# ranback_top.net
KiCad netlist of a schematic drawn in EAGLE
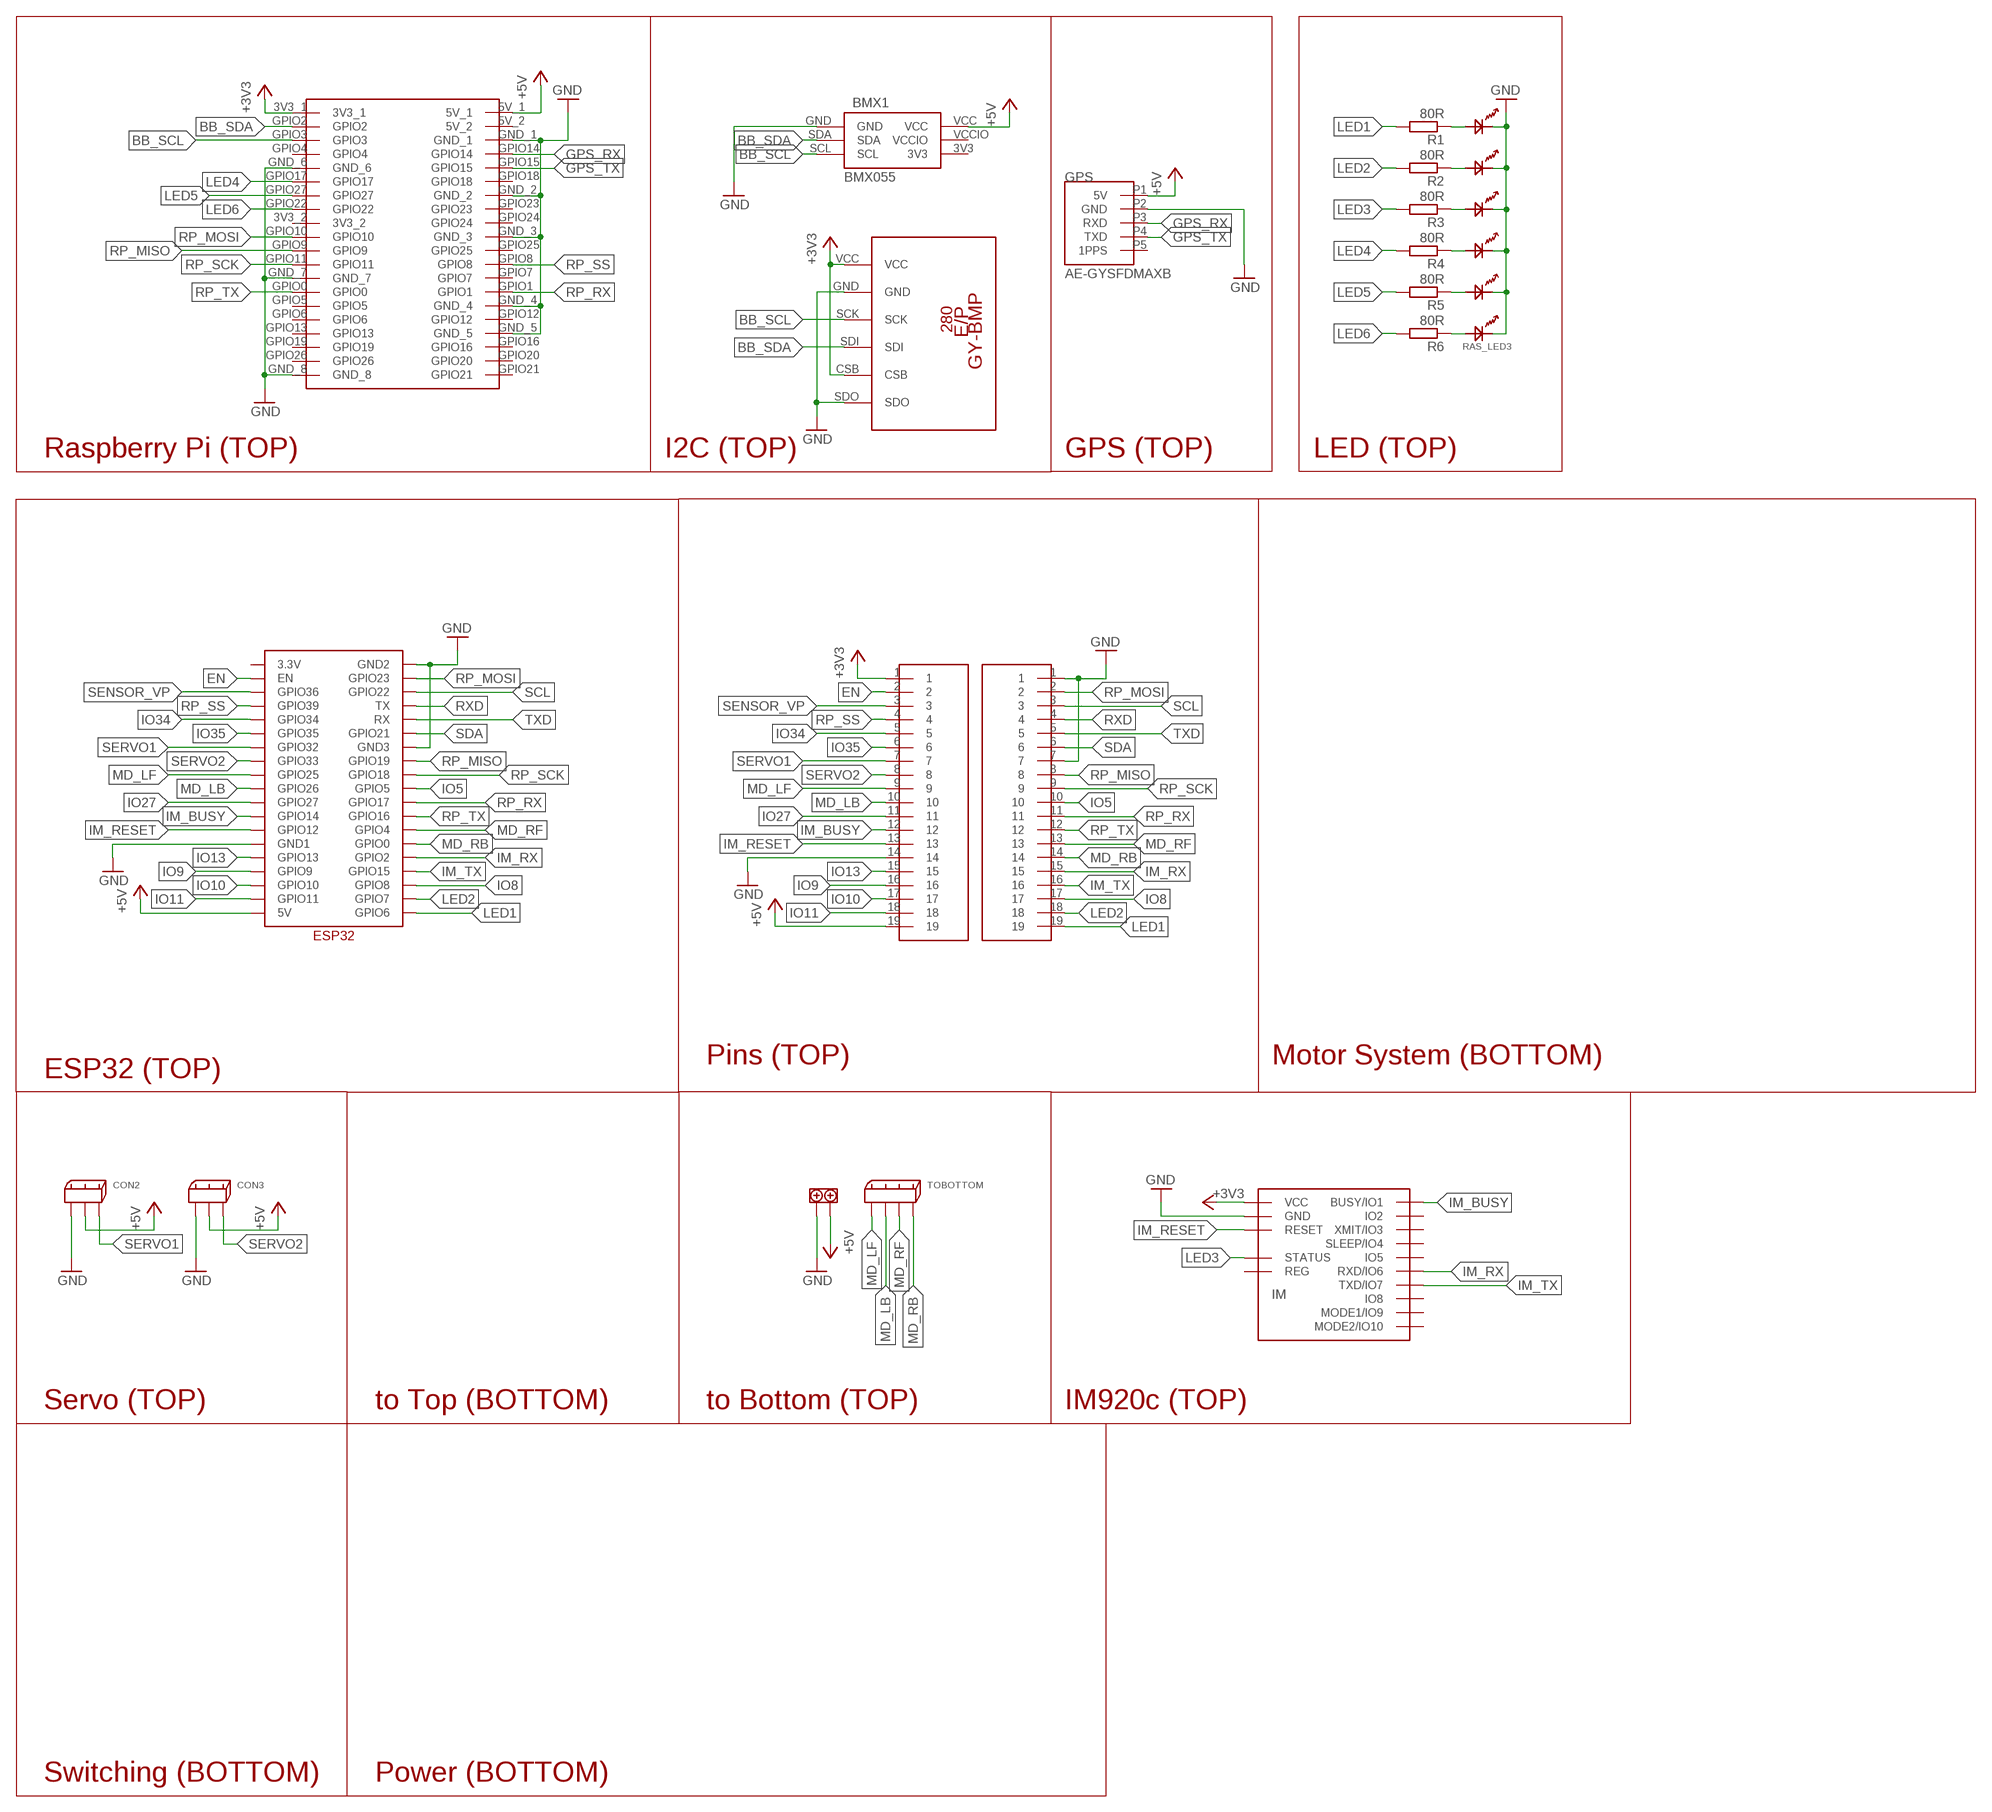
[diagram p0: schematic, sheet 1]

(export (version "E")
  (design (tool "Eeschema 10.0.6"))
  (components
    (comp (ref "BMX1")
      (value "BMX055")
      (footprint "eagle-import:BMX055")
      (libsource (lib "eagle-import") (part "BMX055"))
    )
    (comp (ref "CON2")
      (value "2.5_MINI-SPOX_3PIN")
      (footprint "eagle-import:2.5_MINI-SPOX_3PIN")
      (libsource (lib "eagle-import") (part "2.5_MINI-SPOX_3PIN"))
    )
    (comp (ref "CON3")
      (value "2.5_MINI-SPOX_3PIN")
      (footprint "eagle-import:2.5_MINI-SPOX_3PIN")
      (libsource (lib "eagle-import") (part "2.5_MINI-SPOX_3PIN"))
    )
    (comp (ref "ESP_LED1")
      (value "OSXX1608C1A")
      (footprint "eagle-import:OSXX1608C1A")
      (libsource (lib "eagle-import") (part "OSXX1608C1A"))
    )
    (comp (ref "ESP_LED2")
      (value "OSXX1608C1A")
      (footprint "eagle-import:OSXX1608C1A")
      (libsource (lib "eagle-import") (part "OSXX1608C1A"))
    )
    (comp (ref "GPS")
      (value "AE-GYSFDMAXB")
      (footprint "eagle-import:AE-GYSFDMAXB")
      (libsource (lib "eagle-import") (part "AE-GYSFDMAXB"))
    )
    (comp (ref "IM")
      (value "IM920C")
      (footprint "eagle-import:IM920C")
      (libsource (lib "eagle-import") (part "IM920C"))
    )
    (comp (ref "IMCHECK")
      (value "OSXX1608C1A")
      (footprint "eagle-import:OSXX1608C1A")
      (libsource (lib "eagle-import") (part "OSXX1608C1A"))
    )
    (comp (ref "PIN_L")
      (value "19_2.54")
      (footprint "eagle-import:19_2.54")
      (libsource (lib "eagle-import") (part "19_2.54"))
    )
    (comp (ref "PIN_R")
      (value "19_2.54")
      (footprint "eagle-import:19_2.54")
      (libsource (lib "eagle-import") (part "19_2.54"))
    )
    (comp (ref "R1")
      (value "80R")
      (footprint "eagle-import:0207_10")
      (libsource (lib "eagle-import") (part "R-EU_0207/10"))
    )
    (comp (ref "R2")
      (value "80R")
      (footprint "eagle-import:0207_10")
      (libsource (lib "eagle-import") (part "R-EU_0207/10"))
    )
    (comp (ref "R3")
      (value "80R")
      (footprint "eagle-import:0207_10")
      (libsource (lib "eagle-import") (part "R-EU_0207/10"))
    )
    (comp (ref "R4")
      (value "80R")
      (footprint "eagle-import:0207_10")
      (libsource (lib "eagle-import") (part "R-EU_0207/10"))
    )
    (comp (ref "R5")
      (value "80R")
      (footprint "eagle-import:0207_10")
      (libsource (lib "eagle-import") (part "R-EU_0207/10"))
    )
    (comp (ref "R6")
      (value "80R")
      (footprint "eagle-import:0207_10")
      (libsource (lib "eagle-import") (part "R-EU_0207/10"))
    )
    (comp (ref "RASPBERRYPI_4B")
      (value "RASPBERRYPI4B")
      (footprint "eagle-import:RASPBERRYPI4B")
      (libsource (lib "eagle-import") (part "RASPBERRYPI4B"))
    )
    (comp (ref "RAS_LED1")
      (value "OSXX1608C1A")
      (footprint "eagle-import:OSXX1608C1A")
      (libsource (lib "eagle-import") (part "OSXX1608C1A"))
    )
    (comp (ref "RAS_LED2")
      (value "OSXX1608C1A")
      (footprint "eagle-import:OSXX1608C1A")
      (libsource (lib "eagle-import") (part "OSXX1608C1A"))
    )
    (comp (ref "RAS_LED3")
      (value "OSXX1608C1A")
      (footprint "eagle-import:OSXX1608C1A")
      (libsource (lib "eagle-import") (part "OSXX1608C1A"))
    )
    (comp (ref "TM5")
      (value "TERMINAL_SLOPED_2PIN")
      (footprint "eagle-import:TERMINAL_SLOPED_2PIN")
      (libsource (lib "eagle-import") (part "TERMINAL_SLOPED_2PIN"))
    )
    (comp (ref "TOBOTTOM")
      (value "2.5_MINI-SPOX_4PIN")
      (footprint "eagle-import:2.5_MINI-SPOX_4PIN")
      (libsource (lib "eagle-import") (part "2.5_MINI-SPOX_4PIN"))
    )
    (comp (ref "U$2")
      (value "ESP32")
      (footprint "eagle-import:ESP32")
      (libsource (lib "eagle-import") (part "ESP32"))
    )
    (comp (ref "U$9")
      (value "GY-BPM280")
      (footprint "eagle-import:GY-BMP280-FOOTPRINT")
      (libsource (lib "eagle-import") (part "GY-BPM280"))
    )
  )
  (nets
    (net (code "1") (name "+3V3") (class "Default")
      (node (ref "IM") (pin "$P17") (pinfunction "VCC_$P17") (pintype "bidirectional"))
      (node (ref "PIN_L") (pin "1") (pinfunction "1_1") (pintype "bidirectional"))
      (node (ref "RASPBERRYPI_4B") (pin "3V3_1") (pinfunction "3V3_1_3V3_1") (pintype "bidirectional"))
      (node (ref "U$9") (pin "CSB") (pinfunction "CSB_CSB") (pintype "bidirectional"))
      (node (ref "U$9") (pin "VCC") (pinfunction "VCC_VCC") (pintype "bidirectional"))
    )
    (net (code "2") (name "+5V") (class "Default")
      (node (ref "BMX1") (pin "VCC") (pinfunction "VCC_VCC") (pintype "power_in"))
      (node (ref "CON2") (pin "2") (pinfunction "2_2") (pintype "bidirectional"))
      (node (ref "CON3") (pin "2") (pinfunction "2_2") (pintype "bidirectional"))
      (node (ref "GPS") (pin "P1") (pinfunction "5V_P1") (pintype "bidirectional"))
      (node (ref "PIN_L") (pin "19") (pinfunction "19_19") (pintype "bidirectional"))
      (node (ref "RASPBERRYPI_4B") (pin "5V_1") (pinfunction "5V_1_5V_1") (pintype "bidirectional"))
      (node (ref "TM5") (pin "1") (pinfunction "1_1") (pintype "bidirectional"))
      (node (ref "U$2") (pin "5V") (pinfunction "5V_5V") (pintype "bidirectional"))
    )
    (net (code "3") (name "/3V3") (class "Default")
      (node (ref "BMX1") (pin "3V3") (pinfunction "3V3_3V3") (pintype "power_in"))
    )
    (net (code "4") (name "/VCCIO") (class "Default")
      (node (ref "BMX1") (pin "VCCIO") (pinfunction "VCCIO_VCCIO") (pintype "power_in"))
    )
    (net (code "5") (name "BB_SCL") (class "Default")
      (node (ref "BMX1") (pin "SCL") (pinfunction "SCL_SCL") (pintype "bidirectional"))
      (node (ref "RASPBERRYPI_4B") (pin "GPIO3") (pinfunction "GPIO3_GPIO3") (pintype "bidirectional"))
      (node (ref "U$9") (pin "SCK") (pinfunction "SCK_SCK") (pintype "bidirectional"))
    )
    (net (code "6") (name "BB_SDA") (class "Default")
      (node (ref "BMX1") (pin "SDA") (pinfunction "SDA_SDA") (pintype "bidirectional"))
      (node (ref "RASPBERRYPI_4B") (pin "GPIO2") (pinfunction "GPIO2_GPIO2") (pintype "bidirectional"))
      (node (ref "U$9") (pin "SDI") (pinfunction "SDI_SDI") (pintype "bidirectional"))
    )
    (net (code "7") (name "EN") (class "Default")
      (node (ref "PIN_L") (pin "2") (pinfunction "2_2") (pintype "bidirectional"))
      (node (ref "U$2") (pin "EN") (pinfunction "EN_EN") (pintype "bidirectional"))
    )
    (net (code "8") (name "GND") (class "Default")
      (node (ref "BMX1") (pin "GND") (pinfunction "GND_GND") (pintype "power_in"))
      (node (ref "CON2") (pin "1") (pinfunction "1_1") (pintype "bidirectional"))
      (node (ref "CON3") (pin "1") (pinfunction "1_1") (pintype "bidirectional"))
      (node (ref "ESP_LED1") (pin "CT") (pinfunction "CT_CT") (pintype "bidirectional"))
      (node (ref "ESP_LED2") (pin "CT") (pinfunction "CT_CT") (pintype "bidirectional"))
      (node (ref "GPS") (pin "P2") (pinfunction "GND_P2") (pintype "bidirectional"))
      (node (ref "IM") (pin "$P18") (pinfunction "GND_$P18") (pintype "bidirectional"))
      (node (ref "IMCHECK") (pin "CT") (pinfunction "CT_CT") (pintype "bidirectional"))
      (node (ref "PIN_L") (pin "14") (pinfunction "14_14") (pintype "bidirectional"))
      (node (ref "PIN_R") (pin "1") (pinfunction "1_1") (pintype "bidirectional"))
      (node (ref "PIN_R") (pin "7") (pinfunction "7_7") (pintype "bidirectional"))
      (node (ref "RASPBERRYPI_4B") (pin "GND_1") (pinfunction "GND_1_GND_1") (pintype "bidirectional"))
      (node (ref "RASPBERRYPI_4B") (pin "GND_2") (pinfunction "GND_2_GND_2") (pintype "bidirectional"))
      (node (ref "RASPBERRYPI_4B") (pin "GND_3") (pinfunction "GND_3_GND_3") (pintype "bidirectional"))
      (node (ref "RASPBERRYPI_4B") (pin "GND_4") (pinfunction "GND_4_GND_4") (pintype "bidirectional"))
      (node (ref "RASPBERRYPI_4B") (pin "GND_5") (pinfunction "GND_5_GND_5") (pintype "bidirectional"))
      (node (ref "RASPBERRYPI_4B") (pin "GND_6") (pinfunction "GND_6_GND_6") (pintype "bidirectional"))
      (node (ref "RASPBERRYPI_4B") (pin "GND_7") (pinfunction "GND_7_GND_7") (pintype "bidirectional"))
      (node (ref "RASPBERRYPI_4B") (pin "GND_8") (pinfunction "GND_8_GND_8") (pintype "bidirectional"))
      (node (ref "RAS_LED1") (pin "CT") (pinfunction "CT_CT") (pintype "bidirectional"))
      (node (ref "RAS_LED2") (pin "CT") (pinfunction "CT_CT") (pintype "bidirectional"))
      (node (ref "RAS_LED3") (pin "CT") (pinfunction "CT_CT") (pintype "bidirectional"))
      (node (ref "TM5") (pin "2") (pinfunction "2_2") (pintype "bidirectional"))
      (node (ref "U$2") (pin "GND1") (pinfunction "GND1_GND1") (pintype "bidirectional"))
      (node (ref "U$2") (pin "GND2") (pinfunction "GND2_GND2") (pintype "bidirectional"))
      (node (ref "U$2") (pin "GND3") (pinfunction "GND3_GND3") (pintype "bidirectional"))
      (node (ref "U$9") (pin "GND") (pinfunction "GND_GND") (pintype "bidirectional"))
      (node (ref "U$9") (pin "SDO") (pinfunction "SDO_SDO") (pintype "bidirectional"))
    )
    (net (code "9") (name "GPS_RX") (class "Default")
      (node (ref "GPS") (pin "P3") (pinfunction "RXD_P3") (pintype "bidirectional"))
      (node (ref "RASPBERRYPI_4B") (pin "GPIO14") (pinfunction "GPIO14_GPIO14") (pintype "bidirectional"))
    )
    (net (code "10") (name "GPS_TX") (class "Default")
      (node (ref "GPS") (pin "P4") (pinfunction "TXD_P4") (pintype "bidirectional"))
      (node (ref "RASPBERRYPI_4B") (pin "GPIO15") (pinfunction "GPIO15_GPIO15") (pintype "bidirectional"))
    )
    (net (code "11") (name "IM_BUSY") (class "Default")
      (node (ref "IM") (pin "$P1") (pinfunction "BUSY/IO1_$P1") (pintype "bidirectional"))
      (node (ref "PIN_L") (pin "12") (pinfunction "12_12") (pintype "bidirectional"))
      (node (ref "U$2") (pin "GPIO14") (pinfunction "GPIO14_GPIO14") (pintype "bidirectional"))
    )
    (net (code "12") (name "IM_RESET") (class "Default")
      (node (ref "IM") (pin "$P19") (pinfunction "RESET_$P19") (pintype "bidirectional"))
      (node (ref "PIN_L") (pin "13") (pinfunction "13_13") (pintype "bidirectional"))
      (node (ref "U$2") (pin "GPIO12") (pinfunction "GPIO12_GPIO12") (pintype "bidirectional"))
    )
    (net (code "13") (name "IM_RX") (class "Default")
      (node (ref "IM") (pin "$P6") (pinfunction "RXD/IO6_$P6") (pintype "bidirectional"))
      (node (ref "PIN_R") (pin "15") (pinfunction "15_15") (pintype "bidirectional"))
      (node (ref "U$2") (pin "GPIO2") (pinfunction "GPIO2_GPIO2") (pintype "bidirectional"))
    )
    (net (code "14") (name "IM_TX") (class "Default")
      (node (ref "IM") (pin "$P7") (pinfunction "TXD/IO7_$P7") (pintype "bidirectional"))
      (node (ref "PIN_R") (pin "16") (pinfunction "16_16") (pintype "bidirectional"))
      (node (ref "U$2") (pin "GPIO15") (pinfunction "GPIO15_GPIO15") (pintype "bidirectional"))
    )
    (net (code "15") (name "IO5") (class "Default")
      (node (ref "PIN_R") (pin "10") (pinfunction "10_10") (pintype "bidirectional"))
      (node (ref "U$2") (pin "GPIO5") (pinfunction "GPIO5_GPIO5") (pintype "bidirectional"))
    )
    (net (code "16") (name "IO8") (class "Default")
      (node (ref "PIN_R") (pin "17") (pinfunction "17_17") (pintype "bidirectional"))
      (node (ref "U$2") (pin "GPIO8") (pinfunction "GPIO8_GPIO8") (pintype "bidirectional"))
    )
    (net (code "17") (name "IO9") (class "Default")
      (node (ref "PIN_L") (pin "16") (pinfunction "16_16") (pintype "bidirectional"))
      (node (ref "U$2") (pin "GPIO9") (pinfunction "GPIO9_GPIO9") (pintype "bidirectional"))
    )
    (net (code "18") (name "IO10") (class "Default")
      (node (ref "PIN_L") (pin "17") (pinfunction "17_17") (pintype "bidirectional"))
      (node (ref "U$2") (pin "GPIO10") (pinfunction "GPIO10_GPIO10") (pintype "bidirectional"))
    )
    (net (code "19") (name "IO11") (class "Default")
      (node (ref "PIN_L") (pin "18") (pinfunction "18_18") (pintype "bidirectional"))
      (node (ref "U$2") (pin "GPIO11") (pinfunction "GPIO11_GPIO11") (pintype "bidirectional"))
    )
    (net (code "20") (name "IO13") (class "Default")
      (node (ref "PIN_L") (pin "15") (pinfunction "15_15") (pintype "bidirectional"))
      (node (ref "U$2") (pin "GPIO13") (pinfunction "GPIO13_GPIO13") (pintype "bidirectional"))
    )
    (net (code "21") (name "IO27") (class "Default")
      (node (ref "PIN_L") (pin "11") (pinfunction "11_11") (pintype "bidirectional"))
      (node (ref "U$2") (pin "GPIO27") (pinfunction "GPIO27_GPIO27") (pintype "bidirectional"))
    )
    (net (code "22") (name "IO34") (class "Default")
      (node (ref "PIN_L") (pin "5") (pinfunction "5_5") (pintype "bidirectional"))
      (node (ref "U$2") (pin "GPIO34") (pinfunction "GPIO34_GPIO34") (pintype "bidirectional"))
    )
    (net (code "23") (name "IO35") (class "Default")
      (node (ref "PIN_L") (pin "6") (pinfunction "6_6") (pintype "bidirectional"))
      (node (ref "U$2") (pin "GPIO35") (pinfunction "GPIO35_GPIO35") (pintype "bidirectional"))
    )
    (net (code "24") (name "LED1") (class "Default")
      (node (ref "PIN_R") (pin "19") (pinfunction "19_19") (pintype "bidirectional"))
      (node (ref "R1") (pin "2") (pinfunction "2_2") (pintype "passive"))
      (node (ref "U$2") (pin "GPIO6") (pinfunction "GPIO6_GPIO6") (pintype "bidirectional"))
    )
    (net (code "25") (name "LED2") (class "Default")
      (node (ref "PIN_R") (pin "18") (pinfunction "18_18") (pintype "bidirectional"))
      (node (ref "R2") (pin "2") (pinfunction "2_2") (pintype "passive"))
      (node (ref "U$2") (pin "GPIO7") (pinfunction "GPIO7_GPIO7") (pintype "bidirectional"))
    )
    (net (code "26") (name "LED3") (class "Default")
      (node (ref "IM") (pin "$P15") (pinfunction "STATUS_$P15") (pintype "bidirectional"))
      (node (ref "R3") (pin "2") (pinfunction "2_2") (pintype "passive"))
    )
    (net (code "27") (name "LED4") (class "Default")
      (node (ref "R4") (pin "2") (pinfunction "2_2") (pintype "passive"))
      (node (ref "RASPBERRYPI_4B") (pin "GPIO17") (pinfunction "GPIO17_GPIO17") (pintype "bidirectional"))
    )
    (net (code "28") (name "LED5") (class "Default")
      (node (ref "R5") (pin "2") (pinfunction "2_2") (pintype "passive"))
      (node (ref "RASPBERRYPI_4B") (pin "GPIO27") (pinfunction "GPIO27_GPIO27") (pintype "bidirectional"))
    )
    (net (code "29") (name "LED6") (class "Default")
      (node (ref "R6") (pin "2") (pinfunction "2_2") (pintype "passive"))
      (node (ref "RASPBERRYPI_4B") (pin "GPIO22") (pinfunction "GPIO22_GPIO22") (pintype "bidirectional"))
    )
    (net (code "30") (name "MD_LB") (class "Default")
      (node (ref "PIN_L") (pin "10") (pinfunction "10_10") (pintype "bidirectional"))
      (node (ref "TOBOTTOM") (pin "P$2") (pinfunction "2_P$2") (pintype "bidirectional"))
      (node (ref "U$2") (pin "GPIO26") (pinfunction "GPIO26_GPIO26") (pintype "bidirectional"))
    )
    (net (code "31") (name "MD_LF") (class "Default")
      (node (ref "PIN_L") (pin "9") (pinfunction "9_9") (pintype "bidirectional"))
      (node (ref "TOBOTTOM") (pin "P$1") (pinfunction "1_P$1") (pintype "bidirectional"))
      (node (ref "U$2") (pin "GPIO25") (pinfunction "GPIO25_GPIO25") (pintype "bidirectional"))
    )
    (net (code "32") (name "MD_RB") (class "Default")
      (node (ref "PIN_R") (pin "14") (pinfunction "14_14") (pintype "bidirectional"))
      (node (ref "TOBOTTOM") (pin "P$4") (pinfunction "4_P$4") (pintype "bidirectional"))
      (node (ref "U$2") (pin "GPIO0") (pinfunction "GPIO0_GPIO0") (pintype "bidirectional"))
    )
    (net (code "33") (name "MD_RF") (class "Default")
      (node (ref "PIN_R") (pin "13") (pinfunction "13_13") (pintype "bidirectional"))
      (node (ref "TOBOTTOM") (pin "P$3") (pinfunction "3_P$3") (pintype "bidirectional"))
      (node (ref "U$2") (pin "GPIO4") (pinfunction "GPIO4_GPIO4") (pintype "bidirectional"))
    )
    (net (code "34") (name "Net-(ESP_LED1-PadAN)") (class "Default")
      (node (ref "ESP_LED1") (pin "AN") (pinfunction "AN_AN") (pintype "bidirectional"))
      (node (ref "R1") (pin "1") (pinfunction "1_1") (pintype "passive"))
    )
    (net (code "35") (name "Net-(ESP_LED2-PadAN)") (class "Default")
      (node (ref "ESP_LED2") (pin "AN") (pinfunction "AN_AN") (pintype "bidirectional"))
      (node (ref "R2") (pin "1") (pinfunction "1_1") (pintype "passive"))
    )
    (net (code "36") (name "Net-(IMCHECK-PadAN)") (class "Default")
      (node (ref "IMCHECK") (pin "AN") (pinfunction "AN_AN") (pintype "bidirectional"))
      (node (ref "R3") (pin "1") (pinfunction "1_1") (pintype "passive"))
    )
    (net (code "37") (name "Net-(R4-Pad1)") (class "Default")
      (node (ref "R4") (pin "1") (pinfunction "1_1") (pintype "passive"))
      (node (ref "RAS_LED1") (pin "AN") (pinfunction "AN_AN") (pintype "bidirectional"))
    )
    (net (code "38") (name "Net-(R5-Pad1)") (class "Default")
      (node (ref "R5") (pin "1") (pinfunction "1_1") (pintype "passive"))
      (node (ref "RAS_LED2") (pin "AN") (pinfunction "AN_AN") (pintype "bidirectional"))
    )
    (net (code "39") (name "Net-(R6-Pad1)") (class "Default")
      (node (ref "R6") (pin "1") (pinfunction "1_1") (pintype "passive"))
      (node (ref "RAS_LED3") (pin "AN") (pinfunction "AN_AN") (pintype "bidirectional"))
    )
    (net (code "40") (name "RP_MISO") (class "Default")
      (node (ref "PIN_R") (pin "8") (pinfunction "8_8") (pintype "bidirectional"))
      (node (ref "RASPBERRYPI_4B") (pin "GPIO9") (pinfunction "GPIO9_GPIO9") (pintype "bidirectional"))
      (node (ref "U$2") (pin "GPIO19") (pinfunction "GPIO19_GPIO19") (pintype "bidirectional"))
    )
    (net (code "41") (name "RP_MOSI") (class "Default")
      (node (ref "PIN_R") (pin "2") (pinfunction "2_2") (pintype "bidirectional"))
      (node (ref "RASPBERRYPI_4B") (pin "GPIO10") (pinfunction "GPIO10_GPIO10") (pintype "bidirectional"))
      (node (ref "U$2") (pin "GPIO23") (pinfunction "GPIO23_GPIO23") (pintype "bidirectional"))
    )
    (net (code "42") (name "RP_RX") (class "Default")
      (node (ref "PIN_R") (pin "11") (pinfunction "11_11") (pintype "bidirectional"))
      (node (ref "RASPBERRYPI_4B") (pin "GPIO1") (pinfunction "GPIO1_GPIO1") (pintype "bidirectional"))
      (node (ref "U$2") (pin "GPIO17") (pinfunction "GPIO17_GPIO17") (pintype "bidirectional"))
    )
    (net (code "43") (name "RP_SCK") (class "Default")
      (node (ref "PIN_R") (pin "9") (pinfunction "9_9") (pintype "bidirectional"))
      (node (ref "RASPBERRYPI_4B") (pin "GPIO11") (pinfunction "GPIO11_GPIO11") (pintype "bidirectional"))
      (node (ref "U$2") (pin "GPIO18") (pinfunction "GPIO18_GPIO18") (pintype "bidirectional"))
    )
    (net (code "44") (name "RP_SS") (class "Default")
      (node (ref "PIN_L") (pin "4") (pinfunction "4_4") (pintype "bidirectional"))
      (node (ref "RASPBERRYPI_4B") (pin "GPIO8") (pinfunction "GPIO8_GPIO8") (pintype "bidirectional"))
      (node (ref "U$2") (pin "GPIO39") (pinfunction "GPIO39_GPIO39") (pintype "bidirectional"))
    )
    (net (code "45") (name "RP_TX") (class "Default")
      (node (ref "PIN_R") (pin "12") (pinfunction "12_12") (pintype "bidirectional"))
      (node (ref "RASPBERRYPI_4B") (pin "GPIO0") (pinfunction "GPIO0_GPIO0") (pintype "bidirectional"))
      (node (ref "U$2") (pin "GPIO16") (pinfunction "GPIO16_GPIO16") (pintype "bidirectional"))
    )
    (net (code "46") (name "RXD") (class "Default")
      (node (ref "PIN_R") (pin "4") (pinfunction "4_4") (pintype "bidirectional"))
      (node (ref "U$2") (pin "TX") (pinfunction "TX_TX") (pintype "bidirectional"))
    )
    (net (code "47") (name "SCL") (class "Default")
      (node (ref "PIN_R") (pin "3") (pinfunction "3_3") (pintype "bidirectional"))
      (node (ref "U$2") (pin "GPIO22") (pinfunction "GPIO22_GPIO22") (pintype "bidirectional"))
    )
    (net (code "48") (name "SDA") (class "Default")
      (node (ref "PIN_R") (pin "6") (pinfunction "6_6") (pintype "bidirectional"))
      (node (ref "U$2") (pin "GPIO21") (pinfunction "GPIO21_GPIO21") (pintype "bidirectional"))
    )
    (net (code "49") (name "SENSOR_VP") (class "Default")
      (node (ref "PIN_L") (pin "3") (pinfunction "3_3") (pintype "bidirectional"))
      (node (ref "U$2") (pin "GPIO36") (pinfunction "GPIO36_GPIO36") (pintype "bidirectional"))
    )
    (net (code "50") (name "SERVO1") (class "Default")
      (node (ref "CON2") (pin "3") (pinfunction "3_3") (pintype "bidirectional"))
      (node (ref "PIN_L") (pin "7") (pinfunction "7_7") (pintype "bidirectional"))
      (node (ref "U$2") (pin "GPIO32") (pinfunction "GPIO32_GPIO32") (pintype "bidirectional"))
    )
    (net (code "51") (name "SERVO2") (class "Default")
      (node (ref "CON3") (pin "3") (pinfunction "3_3") (pintype "bidirectional"))
      (node (ref "PIN_L") (pin "8") (pinfunction "8_8") (pintype "bidirectional"))
      (node (ref "U$2") (pin "GPIO33") (pinfunction "GPIO33_GPIO33") (pintype "bidirectional"))
    )
    (net (code "52") (name "TXD") (class "Default")
      (node (ref "PIN_R") (pin "5") (pinfunction "5_5") (pintype "bidirectional"))
      (node (ref "U$2") (pin "RX") (pinfunction "RX_RX") (pintype "bidirectional"))
    )
    (net (code "53") (name "unconnected-(GPS-1PPS-PadP5)") (class "Default")
      (node (ref "GPS") (pin "P5") (pinfunction "1PPS_P5") (pintype "bidirectional"))
    )
    (net (code "54") (name "unconnected-(IM-IO2-Pad$P2)") (class "Default")
      (node (ref "IM") (pin "$P2") (pinfunction "IO2_$P2") (pintype "bidirectional"))
    )
    (net (code "55") (name "unconnected-(IM-IO5-Pad$P5)") (class "Default")
      (node (ref "IM") (pin "$P5") (pinfunction "IO5_$P5") (pintype "bidirectional"))
    )
    (net (code "56") (name "unconnected-(IM-IO8-Pad$P8)") (class "Default")
      (node (ref "IM") (pin "$P8") (pinfunction "IO8_$P8") (pintype "bidirectional"))
    )
    (net (code "57") (name "unconnected-(IM-MODE1{slash}IO9-Pad$P9)") (class "Default")
      (node (ref "IM") (pin "$P9") (pinfunction "MODE1/IO9_$P9") (pintype "bidirectional"))
    )
    (net (code "58") (name "unconnected-(IM-MODE2{slash}IO10-Pad$P10)") (class "Default")
      (node (ref "IM") (pin "$P10") (pinfunction "MODE2/IO10_$P10") (pintype "bidirectional"))
    )
    (net (code "59") (name "unconnected-(IM-REG-Pad$P16)") (class "Default")
      (node (ref "IM") (pin "$P16") (pinfunction "REG_$P16") (pintype "bidirectional"))
    )
    (net (code "60") (name "unconnected-(IM-SLEEP{slash}IO4-Pad$P4)") (class "Default")
      (node (ref "IM") (pin "$P4") (pinfunction "SLEEP/IO4_$P4") (pintype "bidirectional"))
    )
    (net (code "61") (name "unconnected-(IM-XMIT{slash}IO3-Pad$P3)") (class "Default")
      (node (ref "IM") (pin "$P3") (pinfunction "XMIT/IO3_$P3") (pintype "bidirectional"))
    )
    (net (code "62") (name "unconnected-(RASPBERRYPI_4B-Pad3V3_2)") (class "Default")
      (node (ref "RASPBERRYPI_4B") (pin "3V3_2") (pinfunction "3V3_2_3V3_2") (pintype "bidirectional"))
    )
    (net (code "63") (name "unconnected-(RASPBERRYPI_4B-Pad5V_2)") (class "Default")
      (node (ref "RASPBERRYPI_4B") (pin "5V_2") (pinfunction "5V_2_5V_2") (pintype "bidirectional"))
    )
    (net (code "64") (name "unconnected-(RASPBERRYPI_4B-PadGPIO4)") (class "Default")
      (node (ref "RASPBERRYPI_4B") (pin "GPIO4") (pinfunction "GPIO4_GPIO4") (pintype "bidirectional"))
    )
    (net (code "65") (name "unconnected-(RASPBERRYPI_4B-PadGPIO5)") (class "Default")
      (node (ref "RASPBERRYPI_4B") (pin "GPIO5") (pinfunction "GPIO5_GPIO5") (pintype "bidirectional"))
    )
    (net (code "66") (name "unconnected-(RASPBERRYPI_4B-PadGPIO6)") (class "Default")
      (node (ref "RASPBERRYPI_4B") (pin "GPIO6") (pinfunction "GPIO6_GPIO6") (pintype "bidirectional"))
    )
    (net (code "67") (name "unconnected-(RASPBERRYPI_4B-PadGPIO7)") (class "Default")
      (node (ref "RASPBERRYPI_4B") (pin "GPIO7") (pinfunction "GPIO7_GPIO7") (pintype "bidirectional"))
    )
    (net (code "68") (name "unconnected-(RASPBERRYPI_4B-PadGPIO12)") (class "Default")
      (node (ref "RASPBERRYPI_4B") (pin "GPIO12") (pinfunction "GPIO12_GPIO12") (pintype "bidirectional"))
    )
    (net (code "69") (name "unconnected-(RASPBERRYPI_4B-PadGPIO13)") (class "Default")
      (node (ref "RASPBERRYPI_4B") (pin "GPIO13") (pinfunction "GPIO13_GPIO13") (pintype "bidirectional"))
    )
    (net (code "70") (name "unconnected-(RASPBERRYPI_4B-PadGPIO16)") (class "Default")
      (node (ref "RASPBERRYPI_4B") (pin "GPIO16") (pinfunction "GPIO16_GPIO16") (pintype "bidirectional"))
    )
    (net (code "71") (name "unconnected-(RASPBERRYPI_4B-PadGPIO18)") (class "Default")
      (node (ref "RASPBERRYPI_4B") (pin "GPIO18") (pinfunction "GPIO18_GPIO18") (pintype "bidirectional"))
    )
    (net (code "72") (name "unconnected-(RASPBERRYPI_4B-PadGPIO19)") (class "Default")
      (node (ref "RASPBERRYPI_4B") (pin "GPIO19") (pinfunction "GPIO19_GPIO19") (pintype "bidirectional"))
    )
    (net (code "73") (name "unconnected-(RASPBERRYPI_4B-PadGPIO20)") (class "Default")
      (node (ref "RASPBERRYPI_4B") (pin "GPIO20") (pinfunction "GPIO20_GPIO20") (pintype "bidirectional"))
    )
    (net (code "74") (name "unconnected-(RASPBERRYPI_4B-PadGPIO21)") (class "Default")
      (node (ref "RASPBERRYPI_4B") (pin "GPIO21") (pinfunction "GPIO21_GPIO21") (pintype "bidirectional"))
    )
    (net (code "75") (name "unconnected-(RASPBERRYPI_4B-PadGPIO23)") (class "Default")
      (node (ref "RASPBERRYPI_4B") (pin "GPIO23") (pinfunction "GPIO23_GPIO23") (pintype "bidirectional"))
    )
    (net (code "76") (name "unconnected-(RASPBERRYPI_4B-PadGPIO24)") (class "Default")
      (node (ref "RASPBERRYPI_4B") (pin "GPIO24") (pinfunction "GPIO24_GPIO24") (pintype "bidirectional"))
    )
    (net (code "77") (name "unconnected-(RASPBERRYPI_4B-PadGPIO25)") (class "Default")
      (node (ref "RASPBERRYPI_4B") (pin "GPIO25") (pinfunction "GPIO25_GPIO25") (pintype "bidirectional"))
    )
    (net (code "78") (name "unconnected-(RASPBERRYPI_4B-PadGPIO26)") (class "Default")
      (node (ref "RASPBERRYPI_4B") (pin "GPIO26") (pinfunction "GPIO26_GPIO26") (pintype "bidirectional"))
    )
    (net (code "79") (name "unconnected-(U$2-Pad3.3V)") (class "Default")
      (node (ref "U$2") (pin "3.3V") (pinfunction "3.3V_3.3V") (pintype "bidirectional"))
    )
  )
)
